# 7Seg_LED_Display_Driver.net
KiCad netlist of a schematic drawn in Altium Designer
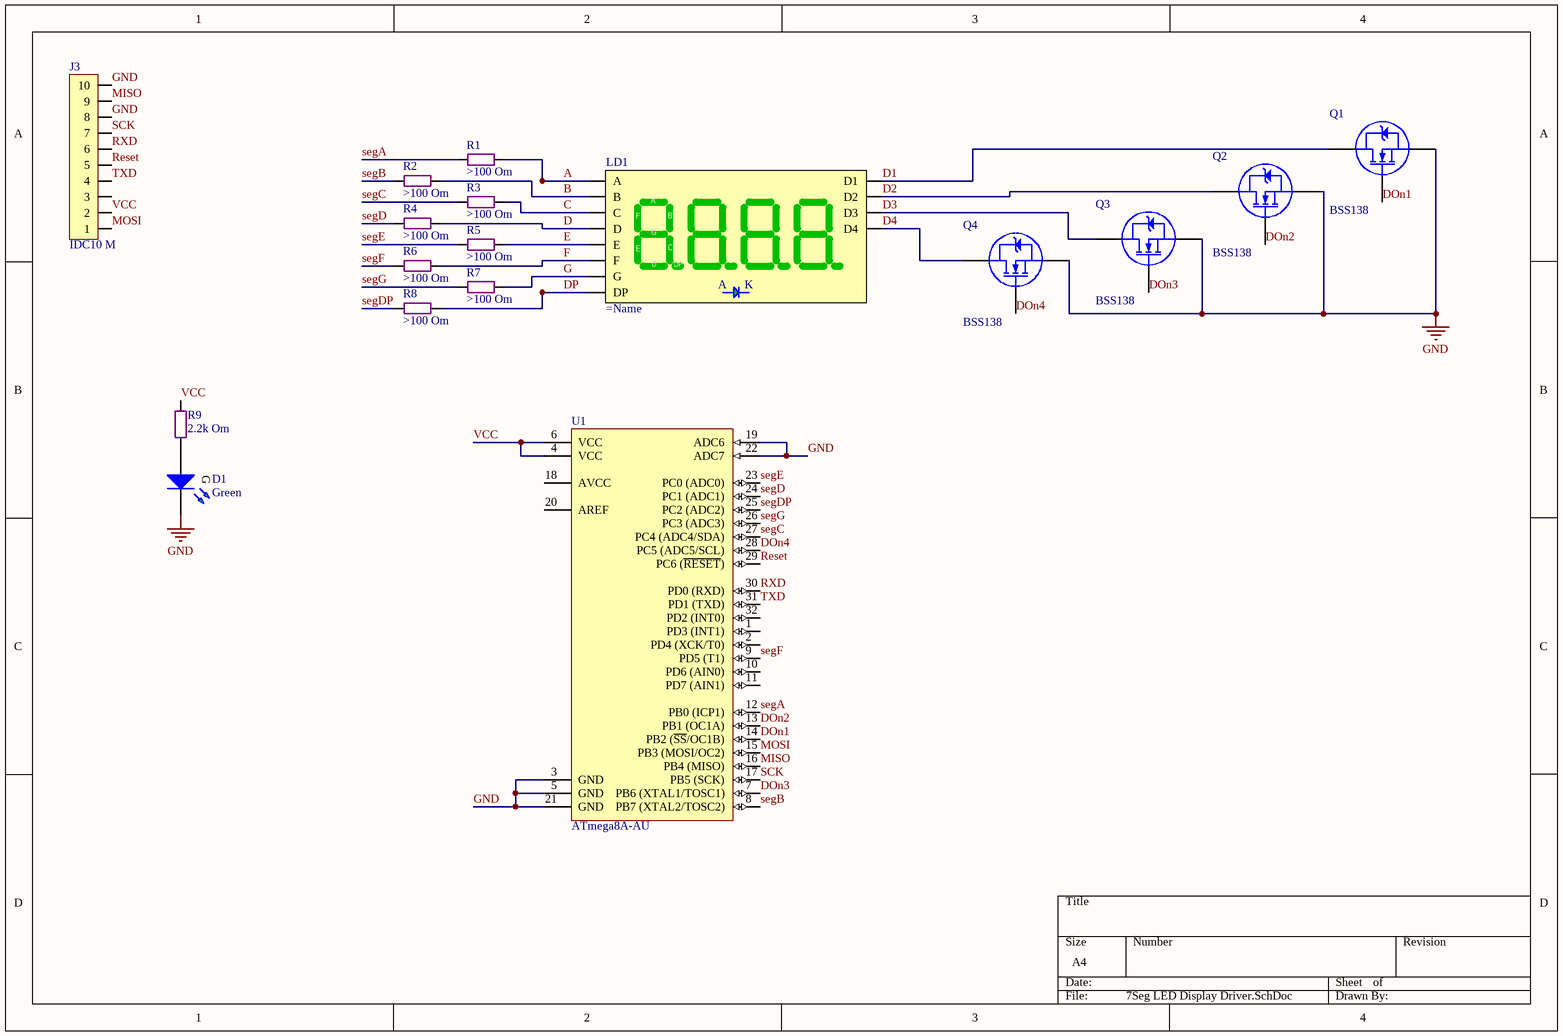
[diagram p0: 7Seg LED Display Driver.SchDoc]

(export (version "E")
  (design (tool "Eeschema 10.0.6"))
  (components
    (comp (ref "D1")
      (value "Green")
      (footprint "LED:LED SMD 0805 Green")
      (description "?2v ?20mA")
      (libsource (lib "LED") (part "Led SMD 0805 Green"))
    )
    (comp (ref "J3")
      (value "IDC10 M")
      (footprint "Connector:LINE 2.54 x 10D (2 x 5) - BH")
      (description "Vert, Dbl line, Male")
      (libsource (lib "Connector") (part "PLD-10 (2 x 5)"))
    )
    (comp (ref "LD1")
      (value "~")
      (footprint "LED:7 seg, Dyn, 4 Digit")
      (description "Dynamic Common Catode/Anode 4 Digits Display")
      (libsource (lib "LED") (part "7 Seg, 4 dig, Dynamic"))
    )
    (comp (ref "Q1")
      (value "BSS138")
      (footprint "GeneralCases:SOT-23")
      (description "N-Channel 50V - 0.7-1Ω - 0.22A")
      (libsource (lib "Transistor") (part "BSS138"))
    )
    (comp (ref "Q2")
      (value "BSS138")
      (footprint "GeneralCases:SOT-23")
      (description "N-Channel 50V - 0.7-1Ω - 0.22A")
      (libsource (lib "Transistor") (part "BSS138"))
    )
    (comp (ref "Q3")
      (value "BSS138")
      (footprint "GeneralCases:SOT-23")
      (description "N-Channel 50V - 0.7-1Ω - 0.22A")
      (libsource (lib "Transistor") (part "BSS138"))
    )
    (comp (ref "Q4")
      (value "BSS138")
      (footprint "GeneralCases:SOT-23")
      (description "N-Channel 50V - 0.7-1Ω - 0.22A")
      (libsource (lib "Transistor") (part "BSS138"))
    )
    (comp (ref "R1")
      (value ">100 Om")
      (footprint "PassiveComponents:SMD 0805 (2012)")
      (libsource (lib "PassiveComponents") (part "Res All Types"))
    )
    (comp (ref "R2")
      (value ">100 Om")
      (footprint "PassiveComponents:SMD 0805 (2012)")
      (libsource (lib "PassiveComponents") (part "Res All Types"))
    )
    (comp (ref "R3")
      (value ">100 Om")
      (footprint "PassiveComponents:SMD 0805 (2012)")
      (libsource (lib "PassiveComponents") (part "Res All Types"))
    )
    (comp (ref "R4")
      (value ">100 Om")
      (footprint "PassiveComponents:SMD 0805 (2012)")
      (libsource (lib "PassiveComponents") (part "Res All Types"))
    )
    (comp (ref "R5")
      (value ">100 Om")
      (footprint "PassiveComponents:SMD 0805 (2012)")
      (libsource (lib "PassiveComponents") (part "Res All Types"))
    )
    (comp (ref "R6")
      (value ">100 Om")
      (footprint "PassiveComponents:SMD 0805 (2012)")
      (libsource (lib "PassiveComponents") (part "Res All Types"))
    )
    (comp (ref "R7")
      (value ">100 Om")
      (footprint "PassiveComponents:SMD 0805 (2012)")
      (libsource (lib "PassiveComponents") (part "Res All Types"))
    )
    (comp (ref "R8")
      (value ">100 Om")
      (footprint "PassiveComponents:SMD 0805 (2012)")
      (libsource (lib "PassiveComponents") (part "Res All Types"))
    )
    (comp (ref "R9")
      (value "2.2k Om")
      (footprint "PassiveComponents:SMD 0805 (2012)")
      (libsource (lib "PassiveComponents") (part "Res All Types"))
    )
    (comp (ref "U1")
      (value "ATmega8A-AU")
      (footprint "32A_N")
      (fields (field (name "PUBLISHER") "Altium Limited"))
      (libsource (lib "Atmel Microcontroller 8-Bit megaAVR") (part "ATmega8A-AU"))
    )
  )
  (nets
    (net (code "1") (name "/A") (class "Default")
      (node (ref "LD1") (pin "A") (pinfunction "A_A") (pintype "passive"))
      (node (ref "R1") (pin "2") (pinfunction "2_2") (pintype "passive"))
    )
    (net (code "2") (name "/B") (class "Default")
      (node (ref "LD1") (pin "B") (pinfunction "B_B") (pintype "passive"))
      (node (ref "R2") (pin "2") (pinfunction "2_2") (pintype "passive"))
    )
    (net (code "3") (name "/C") (class "Default")
      (node (ref "LD1") (pin "C") (pinfunction "C_C") (pintype "passive"))
      (node (ref "R3") (pin "2") (pinfunction "2_2") (pintype "passive"))
    )
    (net (code "4") (name "/D") (class "Default")
      (node (ref "LD1") (pin "D") (pinfunction "D_D") (pintype "passive"))
      (node (ref "R4") (pin "2") (pinfunction "2_2") (pintype "passive"))
    )
    (net (code "5") (name "/D1") (class "Default")
      (node (ref "LD1") (pin "D1") (pinfunction "D1_D1") (pintype "passive"))
      (node (ref "Q1") (pin "2") (pinfunction "D_2") (pintype "passive"))
    )
    (net (code "6") (name "/D2") (class "Default")
      (node (ref "LD1") (pin "D2") (pinfunction "D2_D2") (pintype "passive"))
      (node (ref "Q2") (pin "2") (pinfunction "D_2") (pintype "passive"))
    )
    (net (code "7") (name "/D3") (class "Default")
      (node (ref "LD1") (pin "D3") (pinfunction "D3_D3") (pintype "passive"))
      (node (ref "Q3") (pin "2") (pinfunction "D_2") (pintype "passive"))
    )
    (net (code "8") (name "/D4") (class "Default")
      (node (ref "LD1") (pin "D4") (pinfunction "D4_D4") (pintype "passive"))
      (node (ref "Q4") (pin "2") (pinfunction "D_2") (pintype "passive"))
    )
    (net (code "9") (name "/DOn1") (class "Default")
      (node (ref "Q1") (pin "1") (pinfunction "G_1") (pintype "passive"))
      (node (ref "U1") (pin "14") (pinfunction "PB2_(~{SS}/OC1B)_14") (pintype "bidirectional"))
    )
    (net (code "10") (name "/DOn2") (class "Default")
      (node (ref "Q2") (pin "1") (pinfunction "G_1") (pintype "passive"))
      (node (ref "U1") (pin "13") (pinfunction "PB1_(OC1A)_13") (pintype "bidirectional"))
    )
    (net (code "11") (name "/DOn3") (class "Default")
      (node (ref "Q3") (pin "1") (pinfunction "G_1") (pintype "passive"))
      (node (ref "U1") (pin "7") (pinfunction "PB6_(XTAL1/TOSC1)_7") (pintype "bidirectional"))
    )
    (net (code "12") (name "/DOn4") (class "Default")
      (node (ref "Q4") (pin "1") (pinfunction "G_1") (pintype "passive"))
      (node (ref "U1") (pin "28") (pinfunction "PC5_(ADC5/SCL)_28") (pintype "bidirectional"))
    )
    (net (code "13") (name "/DP") (class "Default")
      (node (ref "LD1") (pin "DP") (pinfunction "DP_DP") (pintype "passive"))
      (node (ref "R8") (pin "2") (pinfunction "2_2") (pintype "passive"))
    )
    (net (code "14") (name "/E") (class "Default")
      (node (ref "LD1") (pin "E") (pinfunction "E_E") (pintype "passive"))
      (node (ref "R5") (pin "2") (pinfunction "2_2") (pintype "passive"))
    )
    (net (code "15") (name "/F") (class "Default")
      (node (ref "LD1") (pin "F") (pinfunction "F_F") (pintype "passive"))
      (node (ref "R6") (pin "2") (pinfunction "2_2") (pintype "passive"))
    )
    (net (code "16") (name "/G") (class "Default")
      (node (ref "LD1") (pin "G") (pinfunction "G_G") (pintype "passive"))
      (node (ref "R7") (pin "2") (pinfunction "2_2") (pintype "passive"))
    )
    (net (code "17") (name "/MISO") (class "Default")
      (node (ref "J3") (pin "9") (pinfunction "9_9") (pintype "passive"))
      (node (ref "U1") (pin "16") (pinfunction "PB4_(MISO)_16") (pintype "bidirectional"))
    )
    (net (code "18") (name "/MOSI") (class "Default")
      (node (ref "J3") (pin "1") (pinfunction "1_1") (pintype "passive"))
      (node (ref "U1") (pin "15") (pinfunction "PB3_(MOSI/OC2)_15") (pintype "bidirectional"))
    )
    (net (code "19") (name "/RXD") (class "Default")
      (node (ref "J3") (pin "6") (pinfunction "6_6") (pintype "passive"))
      (node (ref "U1") (pin "30") (pinfunction "PD0_(RXD)_30") (pintype "bidirectional"))
    )
    (net (code "20") (name "/Reset") (class "Default")
      (node (ref "J3") (pin "5") (pinfunction "5_5") (pintype "passive"))
      (node (ref "U1") (pin "29") (pinfunction "PC6_(~{RESET})_29") (pintype "bidirectional"))
    )
    (net (code "21") (name "/SCK") (class "Default")
      (node (ref "J3") (pin "7") (pinfunction "7_7") (pintype "passive"))
      (node (ref "U1") (pin "17") (pinfunction "PB5_(SCK)_17") (pintype "bidirectional"))
    )
    (net (code "22") (name "/TXD") (class "Default")
      (node (ref "J3") (pin "4") (pinfunction "4_4") (pintype "passive"))
      (node (ref "U1") (pin "31") (pinfunction "PD1_(TXD)_31") (pintype "bidirectional"))
    )
    (net (code "23") (name "/VCC") (class "Default")
      (node (ref "J3") (pin "2") (pinfunction "2_2") (pintype "passive"))
      (node (ref "R9") (pin "1") (pinfunction "1_1") (pintype "passive"))
      (node (ref "U1") (pin "4") (pinfunction "VCC_4") (pintype "power_in"))
      (node (ref "U1") (pin "6") (pinfunction "VCC_6") (pintype "power_in"))
    )
    (net (code "24") (name "/segA") (class "Default")
      (node (ref "R1") (pin "1") (pinfunction "1_1") (pintype "passive"))
      (node (ref "U1") (pin "12") (pinfunction "PB0_(ICP1)_12") (pintype "bidirectional"))
    )
    (net (code "25") (name "/segB") (class "Default")
      (node (ref "R2") (pin "1") (pinfunction "1_1") (pintype "passive"))
      (node (ref "U1") (pin "8") (pinfunction "PB7_(XTAL2/TOSC2)_8") (pintype "bidirectional"))
    )
    (net (code "26") (name "/segC") (class "Default")
      (node (ref "R3") (pin "1") (pinfunction "1_1") (pintype "passive"))
      (node (ref "U1") (pin "27") (pinfunction "PC4_(ADC4/SDA)_27") (pintype "bidirectional"))
    )
    (net (code "27") (name "/segD") (class "Default")
      (node (ref "R4") (pin "1") (pinfunction "1_1") (pintype "passive"))
      (node (ref "U1") (pin "24") (pinfunction "PC1_(ADC1)_24") (pintype "bidirectional"))
    )
    (net (code "28") (name "/segDP") (class "Default")
      (node (ref "R8") (pin "1") (pinfunction "1_1") (pintype "passive"))
      (node (ref "U1") (pin "25") (pinfunction "PC2_(ADC2)_25") (pintype "bidirectional"))
    )
    (net (code "29") (name "/segE") (class "Default")
      (node (ref "R5") (pin "1") (pinfunction "1_1") (pintype "passive"))
      (node (ref "U1") (pin "23") (pinfunction "PC0_(ADC0)_23") (pintype "bidirectional"))
    )
    (net (code "30") (name "/segF") (class "Default")
      (node (ref "R6") (pin "1") (pinfunction "1_1") (pintype "passive"))
      (node (ref "U1") (pin "9") (pinfunction "PD5_(T1)_9") (pintype "bidirectional"))
    )
    (net (code "31") (name "/segG") (class "Default")
      (node (ref "R7") (pin "1") (pinfunction "1_1") (pintype "passive"))
      (node (ref "U1") (pin "26") (pinfunction "PC3_(ADC3)_26") (pintype "bidirectional"))
    )
    (net (code "32") (name "GND") (class "Default")
      (node (ref "D1") (pin "K") (pinfunction "K_K") (pintype "passive"))
      (node (ref "J3") (pin "10") (pinfunction "10_10") (pintype "passive"))
      (node (ref "J3") (pin "8") (pinfunction "8_8") (pintype "passive"))
      (node (ref "Q1") (pin "3") (pinfunction "S_3") (pintype "passive"))
      (node (ref "Q2") (pin "3") (pinfunction "S_3") (pintype "passive"))
      (node (ref "Q3") (pin "3") (pinfunction "S_3") (pintype "passive"))
      (node (ref "Q4") (pin "3") (pinfunction "S_3") (pintype "passive"))
      (node (ref "U1") (pin "19") (pinfunction "ADC6_19") (pintype "input"))
      (node (ref "U1") (pin "21") (pinfunction "GND_21") (pintype "power_in"))
      (node (ref "U1") (pin "22") (pinfunction "ADC7_22") (pintype "input"))
      (node (ref "U1") (pin "3") (pinfunction "GND_3") (pintype "power_in"))
      (node (ref "U1") (pin "5") (pinfunction "GND_5") (pintype "power_in"))
    )
    (net (code "33") (name "Net-(D1-PadA)") (class "Default")
      (node (ref "D1") (pin "A") (pinfunction "A_A") (pintype "passive"))
      (node (ref "R9") (pin "2") (pinfunction "2_2") (pintype "passive"))
    )
    (net (code "34") (name "unconnected-(J3-Pad3)") (class "Default")
      (node (ref "J3") (pin "3") (pinfunction "3_3") (pintype "passive"))
    )
    (net (code "35") (name "unconnected-(U1-AREF-Pad20)") (class "Default")
      (node (ref "U1") (pin "20") (pinfunction "AREF_20") (pintype "power_in"))
    )
    (net (code "36") (name "unconnected-(U1-AVCC-Pad18)") (class "Default")
      (node (ref "U1") (pin "18") (pinfunction "AVCC_18") (pintype "power_in"))
    )
    (net (code "37") (name "unconnected-(U1-PD2_(INT0)-Pad32)") (class "Default")
      (node (ref "U1") (pin "32") (pinfunction "PD2_(INT0)_32") (pintype "bidirectional"))
    )
    (net (code "38") (name "unconnected-(U1-PD3_(INT1)-Pad1)") (class "Default")
      (node (ref "U1") (pin "1") (pinfunction "PD3_(INT1)_1") (pintype "bidirectional"))
    )
    (net (code "39") (name "unconnected-(U1-PD4_(XCK{slash}T0)-Pad2)") (class "Default")
      (node (ref "U1") (pin "2") (pinfunction "PD4_(XCK/T0)_2") (pintype "bidirectional"))
    )
    (net (code "40") (name "unconnected-(U1-PD6_(AIN0)-Pad10)") (class "Default")
      (node (ref "U1") (pin "10") (pinfunction "PD6_(AIN0)_10") (pintype "bidirectional"))
    )
    (net (code "41") (name "unconnected-(U1-PD7_(AIN1)-Pad11)") (class "Default")
      (node (ref "U1") (pin "11") (pinfunction "PD7_(AIN1)_11") (pintype "bidirectional"))
    )
  )
)
